# tm7_revG.net
KiCad netlist of a schematic drawn in EAGLE
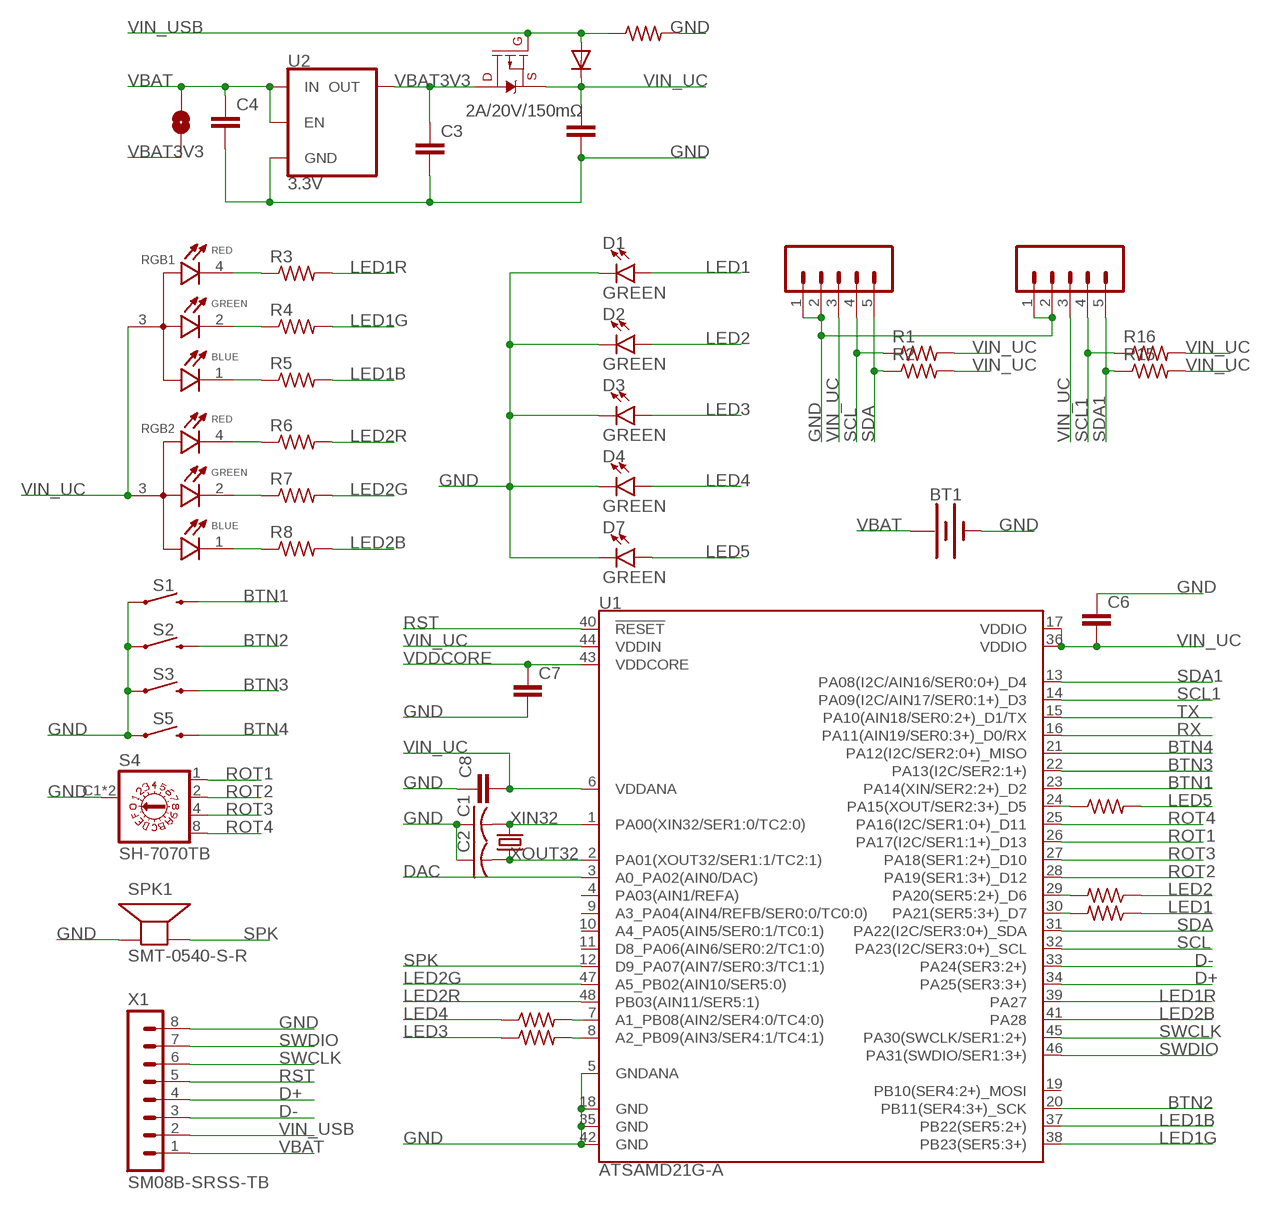
[diagram p0: schematic, sheet 1]

(export (version "E")
  (design (tool "Eeschema 10.0.6"))
  (components
    (comp (ref "BT1")
      (value "BATTERY-20MM_SMD_4LEGS_OVERPASTE_INNER")
      (footprint "eagle-import:BATTCON_20MM_4LEGS_OVERPASTE_INNER")
      (libsource (lib "eagle-import") (part "BATTERY-20MM_SMD_4LEGS_OVERPASTE_INNER"))
    )
    (comp (ref "C1")
      (value "C-USC0603")
      (footprint "eagle-import:C0603")
      (libsource (lib "eagle-import") (part "C-USC0603"))
    )
    (comp (ref "C2")
      (value "C-USC0603")
      (footprint "eagle-import:C0603")
      (libsource (lib "eagle-import") (part "C-USC0603"))
    )
    (comp (ref "C3")
      (value "C-EUC0603")
      (footprint "eagle-import:C0603")
      (libsource (lib "eagle-import") (part "C-EUC0603"))
    )
    (comp (ref "C4")
      (value "C-EUC0603")
      (footprint "eagle-import:C0603")
      (libsource (lib "eagle-import") (part "C-EUC0603"))
    )
    (comp (ref "C6")
      (value "C-EUC0603")
      (footprint "eagle-import:C0603")
      (libsource (lib "eagle-import") (part "C-EUC0603"))
    )
    (comp (ref "C7")
      (value "C-EUC0603")
      (footprint "eagle-import:C0603")
      (libsource (lib "eagle-import") (part "C-EUC0603"))
    )
    (comp (ref "C8")
      (value "C-EUC0603")
      (footprint "eagle-import:C0603")
      (libsource (lib "eagle-import") (part "C-EUC0603"))
    )
    (comp (ref "C9")
      (value "C-EUC0603")
      (footprint "eagle-import:C0603")
      (libsource (lib "eagle-import") (part "C-EUC0603"))
    )
    (comp (ref "D1")
      (value "GREEN")
      (footprint "eagle-import:LED-1206")
      (libsource (lib "eagle-import") (part "LED-GREEN1206"))
    )
    (comp (ref "D2")
      (value "GREEN")
      (footprint "eagle-import:LED-1206")
      (libsource (lib "eagle-import") (part "LED-GREEN1206"))
    )
    (comp (ref "D3")
      (value "GREEN")
      (footprint "eagle-import:LED-1206")
      (libsource (lib "eagle-import") (part "LED-GREEN1206"))
    )
    (comp (ref "D4")
      (value "GREEN")
      (footprint "eagle-import:LED-1206")
      (libsource (lib "eagle-import") (part "LED-GREEN1206"))
    )
    (comp (ref "D7")
      (value "GREEN")
      (footprint "eagle-import:LED-1206")
      (libsource (lib "eagle-import") (part "LED-GREEN1206"))
    )
    (comp (ref "D8")
      (value "DIODESOD-323F")
      (footprint "eagle-import:SOD-323F")
      (libsource (lib "eagle-import") (part "DIODESOD-323F"))
    )
    (comp (ref "JP1")
      (value "JUMPER-SMT_2_NO_NO-SILK")
      (footprint "eagle-import:SMT-JUMPER_2_NO_NO-SILK")
      (libsource (lib "eagle-import") (part "JUMPER-SMT_2_NO_NO-SILK"))
    )
    (comp (ref "LCD1")
      (value "CONN_05VERT_FEMALE_HEADER")
      (footprint "eagle-import:1X05_SMD_VERTICAL_COMBO")
      (libsource (lib "eagle-import") (part "CONN_05VERT_FEMALE_HEADER"))
    )
    (comp (ref "LCD2")
      (value "CONN_05VERT_FEMALE_HEADER")
      (footprint "eagle-import:1X05_SMD_VERTICAL_COMBO")
      (libsource (lib "eagle-import") (part "CONN_05VERT_FEMALE_HEADER"))
    )
    (comp (ref "Q1")
      (value "2A/20V/150mΩ")
      (footprint "eagle-import:SOT26")
      (libsource (lib "eagle-import") (part "MOSFET_PCH_DUAL-DMP2240UDM"))
    )
    (comp (ref "R1")
      (value "R-US_R0603")
      (footprint "eagle-import:R0603")
      (libsource (lib "eagle-import") (part "rcl_334_R-US_R0603"))
    )
    (comp (ref "R2")
      (value "R-US_R0603")
      (footprint "eagle-import:R0603")
      (libsource (lib "eagle-import") (part "rcl_334_R-US_R0603"))
    )
    (comp (ref "R3")
      (value "R-US_R0603")
      (footprint "eagle-import:R0603")
      (libsource (lib "eagle-import") (part "rcl_334_R-US_R0603"))
    )
    (comp (ref "R4")
      (value "R-US_R0603")
      (footprint "eagle-import:R0603")
      (libsource (lib "eagle-import") (part "rcl_334_R-US_R0603"))
    )
    (comp (ref "R5")
      (value "R-US_R0603")
      (footprint "eagle-import:R0603")
      (libsource (lib "eagle-import") (part "rcl_334_R-US_R0603"))
    )
    (comp (ref "R6")
      (value "R-US_R0603")
      (footprint "eagle-import:R0603")
      (libsource (lib "eagle-import") (part "rcl_334_R-US_R0603"))
    )
    (comp (ref "R7")
      (value "R-US_R0603")
      (footprint "eagle-import:R0603")
      (libsource (lib "eagle-import") (part "rcl_334_R-US_R0603"))
    )
    (comp (ref "R8")
      (value "R-US_R0603")
      (footprint "eagle-import:R0603")
      (libsource (lib "eagle-import") (part "rcl_334_R-US_R0603"))
    )
    (comp (ref "R9")
      (value "R-US_R0603")
      (footprint "eagle-import:R0603")
      (libsource (lib "eagle-import") (part "rcl_334_R-US_R0603"))
    )
    (comp (ref "R10")
      (value "R-US_R0603")
      (footprint "eagle-import:R0603")
      (libsource (lib "eagle-import") (part "rcl_334_R-US_R0603"))
    )
    (comp (ref "R11")
      (value "R-US_R0603")
      (footprint "eagle-import:R0603")
      (libsource (lib "eagle-import") (part "rcl_334_R-US_R0603"))
    )
    (comp (ref "R12")
      (value "R-US_R0603")
      (footprint "eagle-import:R0603")
      (libsource (lib "eagle-import") (part "rcl_334_R-US_R0603"))
    )
    (comp (ref "R13")
      (value "R-US_R0603")
      (footprint "eagle-import:R0603")
      (libsource (lib "eagle-import") (part "rcl_334_R-US_R0603"))
    )
    (comp (ref "R14")
      (value "R-US_R0603")
      (footprint "eagle-import:R0603")
      (libsource (lib "eagle-import") (part "R-US_R0603"))
    )
    (comp (ref "R15")
      (value "R-US_R0603")
      (footprint "eagle-import:R0603")
      (libsource (lib "eagle-import") (part "rcl_334_R-US_R0603"))
    )
    (comp (ref "R16")
      (value "R-US_R0603")
      (footprint "eagle-import:R0603")
      (libsource (lib "eagle-import") (part "rcl_334_R-US_R0603"))
    )
    (comp (ref "RGB1")
      (value "EAST1616RGBA3")
      (footprint "eagle-import:LED_EAST1616RGBA3")
      (fields (field (name "MF") "Everlight Electronics"))
      (libsource (lib "eagle-import") (part "EAST1616RGBA3"))
    )
    (comp (ref "RGB2")
      (value "EAST1616RGBA3")
      (footprint "eagle-import:LED_EAST1616RGBA3")
      (fields (field (name "MF") "Everlight Electronics"))
      (libsource (lib "eagle-import") (part "EAST1616RGBA3"))
    )
    (comp (ref "S1")
      (value "MOMENTARY-SWITCH-SPST-SMD-6.0X3.5MM")
      (footprint "eagle-import:TACTILE_SWITCH_SMD_6.0X3.5MM")
      (libsource (lib "eagle-import") (part "MOMENTARY-SWITCH-SPST-SMD-6.0X3.5MM"))
    )
    (comp (ref "S2")
      (value "MOMENTARY-SWITCH-SPST-SMD-6.0X3.5MM")
      (footprint "eagle-import:TACTILE_SWITCH_SMD_6.0X3.5MM")
      (libsource (lib "eagle-import") (part "MOMENTARY-SWITCH-SPST-SMD-6.0X3.5MM"))
    )
    (comp (ref "S3")
      (value "MOMENTARY-SWITCH-SPST-SMD-6.0X3.5MM")
      (footprint "eagle-import:TACTILE_SWITCH_SMD_6.0X3.5MM")
      (libsource (lib "eagle-import") (part "MOMENTARY-SWITCH-SPST-SMD-6.0X3.5MM"))
    )
    (comp (ref "S4")
      (value "SH-7070TB")
      (footprint "eagle-import:SH-7070B")
      (fields (field (name "MF") "Nidec Copal"))
      (libsource (lib "eagle-import") (part "SH-7070TB"))
    )
    (comp (ref "S5")
      (value "MOMENTARY-SWITCH-SPST-SMD-6.0X3.5MM")
      (footprint "eagle-import:TACTILE_SWITCH_SMD_6.0X3.5MM")
      (libsource (lib "eagle-import") (part "MOMENTARY-SWITCH-SPST-SMD-6.0X3.5MM"))
    )
    (comp (ref "SPK1")
      (value "SMT-0540-S-R")
      (footprint "eagle-import:SMT-0540-S-R")
      (fields (field (name "MF") "PUI"))
      (libsource (lib "eagle-import") (part "SMT-0540-S-R"))
    )
    (comp (ref "U1")
      (value "ATSAMD21G-A")
      (footprint "eagle-import:TQFP-48")
      (libsource (lib "eagle-import") (part "ATSAMD21G-A"))
    )
    (comp (ref "U2")
      (value "3.3V")
      (footprint "eagle-import:SOT23-5")
      (libsource (lib "eagle-import") (part "V_REG_AP2112K-3.3V"))
    )
    (comp (ref "X1")
      (value "SM08B-SRSS-TB")
      (footprint "eagle-import:SM08B-SRSS-TB")
      (libsource (lib "eagle-import") (part "SM08B-SRSS-TB"))
    )
    (comp (ref "Y1")
      (value "32.768kHz")
      (footprint "eagle-import:CRYSTAL-SMD-3.2X1.5MM")
      (libsource (lib "eagle-import") (part "CRYSTAL-32.768KHZSMD-3.2X1.5"))
    )
  )
  (nets
    (net (code "1") (name "/BTN1") (class "Default")
      (node (ref "S1") (pin "2") (pinfunction "2_2") (pintype "passive"))
      (node (ref "U1") (pin "23") (pinfunction "PA14(XIN/SER2:2+)_D2_23") (pintype "bidirectional"))
    )
    (net (code "2") (name "/BTN2") (class "Default")
      (node (ref "S2") (pin "2") (pinfunction "2_2") (pintype "passive"))
      (node (ref "U1") (pin "20") (pinfunction "PB11(SER4:3+)_SCK_20") (pintype "bidirectional"))
    )
    (net (code "3") (name "/BTN3") (class "Default")
      (node (ref "S3") (pin "2") (pinfunction "2_2") (pintype "passive"))
      (node (ref "U1") (pin "22") (pinfunction "PA13(I2C/SER2:1+)_22") (pintype "bidirectional"))
    )
    (net (code "4") (name "/BTN4") (class "Default")
      (node (ref "S5") (pin "2") (pinfunction "2_2") (pintype "passive"))
      (node (ref "U1") (pin "21") (pinfunction "PA12(I2C/SER2:0+)_MISO_21") (pintype "bidirectional"))
    )
    (net (code "5") (name "/D+") (class "Default")
      (node (ref "U1") (pin "34") (pinfunction "PA25(SER3:3+)_34") (pintype "bidirectional"))
      (node (ref "X1") (pin "4") (pinfunction "4_4") (pintype "passive"))
    )
    (net (code "6") (name "/D-") (class "Default")
      (node (ref "U1") (pin "33") (pinfunction "PA24(SER3:2+)_33") (pintype "bidirectional"))
      (node (ref "X1") (pin "3") (pinfunction "3_3") (pintype "passive"))
    )
    (net (code "7") (name "/DAC") (class "Default")
      (node (ref "U1") (pin "3") (pinfunction "A0_PA02(AIN0/DAC)_3") (pintype "bidirectional"))
    )
    (net (code "8") (name "/GND") (class "Default")
      (node (ref "BT1") (pin "2") (pinfunction "-_2") (pintype "power_in"))
      (node (ref "C1") (pin "1") (pinfunction "1_1") (pintype "passive"))
      (node (ref "C2") (pin "1") (pinfunction "1_1") (pintype "passive"))
      (node (ref "C3") (pin "2") (pinfunction "2_2") (pintype "passive"))
      (node (ref "C4") (pin "2") (pinfunction "2_2") (pintype "passive"))
      (node (ref "C6") (pin "1") (pinfunction "1_1") (pintype "passive"))
      (node (ref "C7") (pin "2") (pinfunction "2_2") (pintype "passive"))
      (node (ref "C8") (pin "1") (pinfunction "1_1") (pintype "passive"))
      (node (ref "C9") (pin "2") (pinfunction "2_2") (pintype "passive"))
      (node (ref "D1") (pin "C") (pinfunction "C_C") (pintype "passive"))
      (node (ref "D2") (pin "C") (pinfunction "C_C") (pintype "passive"))
      (node (ref "D3") (pin "C") (pinfunction "C_C") (pintype "passive"))
      (node (ref "D4") (pin "C") (pinfunction "C_C") (pintype "passive"))
      (node (ref "D7") (pin "C") (pinfunction "C_C") (pintype "passive"))
      (node (ref "LCD1") (pin "1") (pinfunction "1_1") (pintype "passive"))
      (node (ref "LCD1") (pin "2") (pinfunction "2_2") (pintype "passive"))
      (node (ref "LCD2") (pin "1") (pinfunction "1_1") (pintype "passive"))
      (node (ref "LCD2") (pin "2") (pinfunction "2_2") (pintype "passive"))
      (node (ref "R14") (pin "2") (pinfunction "2_2") (pintype "passive"))
      (node (ref "S1") (pin "1") (pinfunction "1_1") (pintype "passive"))
      (node (ref "S2") (pin "1") (pinfunction "1_1") (pintype "passive"))
      (node (ref "S3") (pin "1") (pinfunction "1_1") (pintype "passive"))
      (node (ref "S4") (pin "C1") (pinfunction "C_C1") (pintype "passive"))
      (node (ref "S4") (pin "C2") (pinfunction "C_C2") (pintype "passive"))
      (node (ref "S5") (pin "1") (pinfunction "1_1") (pintype "passive"))
      (node (ref "SPK1") (pin "-") (pinfunction "+_-") (pintype "passive"))
      (node (ref "U1") (pin "18") (pinfunction "GND_18") (pintype "bidirectional"))
      (node (ref "U1") (pin "35") (pinfunction "GND_35") (pintype "bidirectional"))
      (node (ref "U1") (pin "42") (pinfunction "GND_42") (pintype "bidirectional"))
      (node (ref "U1") (pin "5") (pinfunction "GNDANA_5") (pintype "bidirectional"))
      (node (ref "U2") (pin "2") (pinfunction "GND_2") (pintype "input"))
      (node (ref "X1") (pin "8") (pinfunction "8_8") (pintype "passive"))
    )
    (net (code "9") (name "/LED1") (class "Default")
      (node (ref "D1") (pin "A") (pinfunction "A_A") (pintype "passive"))
      (node (ref "R9") (pin "1") (pinfunction "1_1") (pintype "passive"))
    )
    (net (code "10") (name "/LED1B") (class "Default")
      (node (ref "R5") (pin "2") (pinfunction "2_2") (pintype "passive"))
      (node (ref "U1") (pin "37") (pinfunction "PB22(SER5:2+)_37") (pintype "bidirectional"))
    )
    (net (code "11") (name "/LED1G") (class "Default")
      (node (ref "R4") (pin "2") (pinfunction "2_2") (pintype "passive"))
      (node (ref "U1") (pin "38") (pinfunction "PB23(SER5:3+)_38") (pintype "bidirectional"))
    )
    (net (code "12") (name "/LED1R") (class "Default")
      (node (ref "R3") (pin "2") (pinfunction "2_2") (pintype "passive"))
      (node (ref "U1") (pin "39") (pinfunction "PA27_39") (pintype "bidirectional"))
    )
    (net (code "13") (name "/LED2") (class "Default")
      (node (ref "D2") (pin "A") (pinfunction "A_A") (pintype "passive"))
      (node (ref "R10") (pin "1") (pinfunction "1_1") (pintype "passive"))
    )
    (net (code "14") (name "/LED2B") (class "Default")
      (node (ref "R8") (pin "2") (pinfunction "2_2") (pintype "passive"))
      (node (ref "U1") (pin "41") (pinfunction "PA28_41") (pintype "bidirectional"))
    )
    (net (code "15") (name "/LED2G") (class "Default")
      (node (ref "R7") (pin "2") (pinfunction "2_2") (pintype "passive"))
      (node (ref "U1") (pin "47") (pinfunction "A5_PB02(AIN10/SER5:0)_47") (pintype "bidirectional"))
    )
    (net (code "16") (name "/LED2R") (class "Default")
      (node (ref "R6") (pin "2") (pinfunction "2_2") (pintype "passive"))
      (node (ref "U1") (pin "48") (pinfunction "PB03(AIN11/SER5:1)_48") (pintype "bidirectional"))
    )
    (net (code "17") (name "/LED3") (class "Default")
      (node (ref "D3") (pin "A") (pinfunction "A_A") (pintype "passive"))
      (node (ref "R11") (pin "1") (pinfunction "1_1") (pintype "passive"))
    )
    (net (code "18") (name "/LED4") (class "Default")
      (node (ref "D4") (pin "A") (pinfunction "A_A") (pintype "passive"))
      (node (ref "R12") (pin "1") (pinfunction "1_1") (pintype "passive"))
    )
    (net (code "19") (name "/LED5") (class "Default")
      (node (ref "D7") (pin "A") (pinfunction "A_A") (pintype "passive"))
      (node (ref "R13") (pin "2") (pinfunction "2_2") (pintype "passive"))
    )
    (net (code "20") (name "/ROT1") (class "Default")
      (node (ref "S4") (pin "1") (pinfunction "1_1") (pintype "passive"))
      (node (ref "U1") (pin "26") (pinfunction "PA17(I2C/SER1:1+)_D13_26") (pintype "bidirectional"))
    )
    (net (code "21") (name "/ROT2") (class "Default")
      (node (ref "S4") (pin "2") (pinfunction "2_2") (pintype "passive"))
      (node (ref "U1") (pin "28") (pinfunction "PA19(SER1:3+)_D12_28") (pintype "bidirectional"))
    )
    (net (code "22") (name "/ROT3") (class "Default")
      (node (ref "S4") (pin "4") (pinfunction "4_4") (pintype "passive"))
      (node (ref "U1") (pin "27") (pinfunction "PA18(SER1:2+)_D10_27") (pintype "bidirectional"))
    )
    (net (code "23") (name "/ROT4") (class "Default")
      (node (ref "S4") (pin "8") (pinfunction "8_8") (pintype "passive"))
      (node (ref "U1") (pin "25") (pinfunction "PA16(I2C/SER1:0+)_D11_25") (pintype "bidirectional"))
    )
    (net (code "24") (name "/RST") (class "Default")
      (node (ref "U1") (pin "40") (pinfunction "~{RESET}_40") (pintype "bidirectional"))
      (node (ref "X1") (pin "5") (pinfunction "5_5") (pintype "passive"))
    )
    (net (code "25") (name "/RX") (class "Default")
      (node (ref "U1") (pin "16") (pinfunction "PA11(AIN19/SER0:3+)_D0/RX_16") (pintype "bidirectional"))
    )
    (net (code "26") (name "/SCL") (class "Default")
      (node (ref "LCD1") (pin "4") (pinfunction "4_4") (pintype "passive"))
      (node (ref "R1") (pin "1") (pinfunction "1_1") (pintype "passive"))
      (node (ref "U1") (pin "32") (pinfunction "PA23(I2C/SER3:0+)_SCL_32") (pintype "bidirectional"))
    )
    (net (code "27") (name "/SCL1") (class "Default")
      (node (ref "LCD2") (pin "4") (pinfunction "4_4") (pintype "passive"))
      (node (ref "R16") (pin "1") (pinfunction "1_1") (pintype "passive"))
      (node (ref "U1") (pin "14") (pinfunction "PA09(I2C/AIN17/SER0:1+)_D3_14") (pintype "bidirectional"))
    )
    (net (code "28") (name "/SDA") (class "Default")
      (node (ref "LCD1") (pin "5") (pinfunction "5_5") (pintype "passive"))
      (node (ref "R2") (pin "1") (pinfunction "1_1") (pintype "passive"))
      (node (ref "U1") (pin "31") (pinfunction "PA22(I2C/SER3:0+)_SDA_31") (pintype "bidirectional"))
    )
    (net (code "29") (name "/SDA1") (class "Default")
      (node (ref "LCD2") (pin "5") (pinfunction "5_5") (pintype "passive"))
      (node (ref "R15") (pin "1") (pinfunction "1_1") (pintype "passive"))
      (node (ref "U1") (pin "13") (pinfunction "PA08(I2C/AIN16/SER0:0+)_D4_13") (pintype "bidirectional"))
    )
    (net (code "30") (name "/SPK") (class "Default")
      (node (ref "SPK1") (pin "+") (pinfunction "-_+") (pintype "passive"))
      (node (ref "U1") (pin "12") (pinfunction "D9_PA07(AIN7/SER0:3/TC1:1)_12") (pintype "bidirectional"))
    )
    (net (code "31") (name "/SWCLK") (class "Default")
      (node (ref "U1") (pin "45") (pinfunction "PA30(SWCLK/SER1:2+)_45") (pintype "bidirectional"))
      (node (ref "X1") (pin "6") (pinfunction "6_6") (pintype "passive"))
    )
    (net (code "32") (name "/SWDIO") (class "Default")
      (node (ref "U1") (pin "46") (pinfunction "PA31(SWDIO/SER1:3+)_46") (pintype "bidirectional"))
      (node (ref "X1") (pin "7") (pinfunction "7_7") (pintype "passive"))
    )
    (net (code "33") (name "/TX") (class "Default")
      (node (ref "U1") (pin "15") (pinfunction "PA10(AIN18/SER0:2+)_D1/TX_15") (pintype "bidirectional"))
    )
    (net (code "34") (name "/VBAT") (class "Default")
      (node (ref "BT1") (pin "1") (pinfunction "+_1") (pintype "power_in"))
      (node (ref "C4") (pin "1") (pinfunction "1_1") (pintype "passive"))
      (node (ref "JP1") (pin "2") (pinfunction "2_2") (pintype "passive"))
      (node (ref "U2") (pin "1") (pinfunction "IN_1") (pintype "input"))
      (node (ref "U2") (pin "3") (pinfunction "EN_3") (pintype "input"))
      (node (ref "X1") (pin "1") (pinfunction "1_1") (pintype "passive"))
    )
    (net (code "35") (name "/VBAT3V3") (class "Default")
      (node (ref "C3") (pin "1") (pinfunction "1_1") (pintype "passive"))
      (node (ref "JP1") (pin "1") (pinfunction "1_1") (pintype "passive"))
      (node (ref "Q1") (pin "D1") (pinfunction "D_D1") (pintype "bidirectional"))
      (node (ref "U2") (pin "5") (pinfunction "OUT_5") (pintype "passive"))
    )
    (net (code "36") (name "/VDDCORE") (class "Default")
      (node (ref "C7") (pin "1") (pinfunction "1_1") (pintype "passive"))
      (node (ref "U1") (pin "43") (pinfunction "VDDCORE_43") (pintype "bidirectional"))
    )
    (net (code "37") (name "/VIN_UC") (class "Default")
      (node (ref "C6") (pin "2") (pinfunction "2_2") (pintype "passive"))
      (node (ref "C8") (pin "2") (pinfunction "2_2") (pintype "passive"))
      (node (ref "C9") (pin "1") (pinfunction "1_1") (pintype "passive"))
      (node (ref "D8") (pin "C") (pinfunction "C_C") (pintype "passive"))
      (node (ref "LCD1") (pin "3") (pinfunction "3_3") (pintype "passive"))
      (node (ref "LCD2") (pin "3") (pinfunction "3_3") (pintype "passive"))
      (node (ref "Q1") (pin "S1") (pinfunction "S_S1") (pintype "bidirectional"))
      (node (ref "R1") (pin "2") (pinfunction "2_2") (pintype "passive"))
      (node (ref "R15") (pin "2") (pinfunction "2_2") (pintype "passive"))
      (node (ref "R16") (pin "2") (pinfunction "2_2") (pintype "passive"))
      (node (ref "R2") (pin "2") (pinfunction "2_2") (pintype "passive"))
      (node (ref "RGB1") (pin "3") (pinfunction "A_3") (pintype "passive"))
      (node (ref "RGB2") (pin "3") (pinfunction "A_3") (pintype "passive"))
      (node (ref "U1") (pin "17") (pinfunction "VDDIO_17") (pintype "bidirectional"))
      (node (ref "U1") (pin "36") (pinfunction "VDDIO_36") (pintype "bidirectional"))
      (node (ref "U1") (pin "44") (pinfunction "VDDIN_44") (pintype "bidirectional"))
      (node (ref "U1") (pin "6") (pinfunction "VDDANA_6") (pintype "bidirectional"))
    )
    (net (code "38") (name "/VIN_USB") (class "Default")
      (node (ref "D8") (pin "A") (pinfunction "A_A") (pintype "passive"))
      (node (ref "Q1") (pin "G1") (pinfunction "G_G1") (pintype "bidirectional"))
      (node (ref "R14") (pin "1") (pinfunction "1_1") (pintype "passive"))
      (node (ref "X1") (pin "2") (pinfunction "2_2") (pintype "passive"))
    )
    (net (code "39") (name "/XIN32") (class "Default")
      (node (ref "C1") (pin "2") (pinfunction "2_2") (pintype "passive"))
      (node (ref "U1") (pin "1") (pinfunction "PA00(XIN32/SER1:0/TC2:0)_1") (pintype "bidirectional"))
      (node (ref "Y1") (pin "P$2") (pinfunction "2_P$2") (pintype "passive"))
    )
    (net (code "40") (name "/XOUT32") (class "Default")
      (node (ref "C2") (pin "2") (pinfunction "2_2") (pintype "passive"))
      (node (ref "U1") (pin "2") (pinfunction "PA01(XOUT32/SER1:1/TC2:1)_2") (pintype "bidirectional"))
      (node (ref "Y1") (pin "P$1") (pinfunction "1_P$1") (pintype "passive"))
    )
    (net (code "41") (name "Net-(RGB1-B_C)") (class "Default")
      (node (ref "R5") (pin "1") (pinfunction "1_1") (pintype "passive"))
      (node (ref "RGB1") (pin "1") (pinfunction "B_C_1") (pintype "passive"))
    )
    (net (code "42") (name "Net-(RGB1-G_C)") (class "Default")
      (node (ref "R4") (pin "1") (pinfunction "1_1") (pintype "passive"))
      (node (ref "RGB1") (pin "2") (pinfunction "G_C_2") (pintype "passive"))
    )
    (net (code "43") (name "Net-(RGB1-R_C)") (class "Default")
      (node (ref "R3") (pin "1") (pinfunction "1_1") (pintype "passive"))
      (node (ref "RGB1") (pin "4") (pinfunction "R_C_4") (pintype "passive"))
    )
    (net (code "44") (name "Net-(RGB2-B_C)") (class "Default")
      (node (ref "R8") (pin "1") (pinfunction "1_1") (pintype "passive"))
      (node (ref "RGB2") (pin "1") (pinfunction "B_C_1") (pintype "passive"))
    )
    (net (code "45") (name "Net-(RGB2-G_C)") (class "Default")
      (node (ref "R7") (pin "1") (pinfunction "1_1") (pintype "passive"))
      (node (ref "RGB2") (pin "2") (pinfunction "G_C_2") (pintype "passive"))
    )
    (net (code "46") (name "Net-(RGB2-R_C)") (class "Default")
      (node (ref "R6") (pin "1") (pinfunction "1_1") (pintype "passive"))
      (node (ref "RGB2") (pin "4") (pinfunction "R_C_4") (pintype "passive"))
    )
    (net (code "47") (name "Net-(U1-A1_PB08(AIN2{slash}SER4:0{slash}TC4:0))") (class "Default")
      (node (ref "R12") (pin "2") (pinfunction "2_2") (pintype "passive"))
      (node (ref "U1") (pin "7") (pinfunction "A1_PB08(AIN2/SER4:0/TC4:0)_7") (pintype "bidirectional"))
    )
    (net (code "48") (name "Net-(U1-A2_PB09(AIN3{slash}SER4:1{slash}TC4:1))") (class "Default")
      (node (ref "R11") (pin "2") (pinfunction "2_2") (pintype "passive"))
      (node (ref "U1") (pin "8") (pinfunction "A2_PB09(AIN3/SER4:1/TC4:1)_8") (pintype "bidirectional"))
    )
    (net (code "49") (name "Net-(U1-PA15(XOUT{slash}SER2:3+)_D5)") (class "Default")
      (node (ref "R13") (pin "1") (pinfunction "1_1") (pintype "passive"))
      (node (ref "U1") (pin "24") (pinfunction "PA15(XOUT/SER2:3+)_D5_24") (pintype "bidirectional"))
    )
    (net (code "50") (name "Net-(U1-PA20(SER5:2+)_D6)") (class "Default")
      (node (ref "R10") (pin "2") (pinfunction "2_2") (pintype "passive"))
      (node (ref "U1") (pin "29") (pinfunction "PA20(SER5:2+)_D6_29") (pintype "bidirectional"))
    )
    (net (code "51") (name "Net-(U1-PA21(SER5:3+)_D7)") (class "Default")
      (node (ref "R9") (pin "2") (pinfunction "2_2") (pintype "passive"))
      (node (ref "U1") (pin "30") (pinfunction "PA21(SER5:3+)_D7_30") (pintype "bidirectional"))
    )
    (net (code "52") (name "unconnected-(U1-A3_PA04(AIN4{slash}REFB{slash}SER0:0{slash}TC0:0)-Pad9)") (class "Default")
      (node (ref "U1") (pin "9") (pinfunction "A3_PA04(AIN4/REFB/SER0:0/TC0:0)_9") (pintype "bidirectional"))
    )
    (net (code "53") (name "unconnected-(U1-A4_PA05(AIN5{slash}SER0:1{slash}TC0:1)-Pad10)") (class "Default")
      (node (ref "U1") (pin "10") (pinfunction "A4_PA05(AIN5/SER0:1/TC0:1)_10") (pintype "bidirectional"))
    )
    (net (code "54") (name "unconnected-(U1-D8_PA06(AIN6{slash}SER0:2{slash}TC1:0)-Pad11)") (class "Default")
      (node (ref "U1") (pin "11") (pinfunction "D8_PA06(AIN6/SER0:2/TC1:0)_11") (pintype "bidirectional"))
    )
    (net (code "55") (name "unconnected-(U1-PA03(AIN1{slash}REFA)-Pad4)") (class "Default")
      (node (ref "U1") (pin "4") (pinfunction "PA03(AIN1/REFA)_4") (pintype "bidirectional"))
    )
    (net (code "56") (name "unconnected-(U1-PB10(SER4:2+)_MOSI-Pad19)") (class "Default")
      (node (ref "U1") (pin "19") (pinfunction "PB10(SER4:2+)_MOSI_19") (pintype "bidirectional"))
    )
  )
)
